# EM.net
KiCad netlist of a schematic drawn in Altium Designer
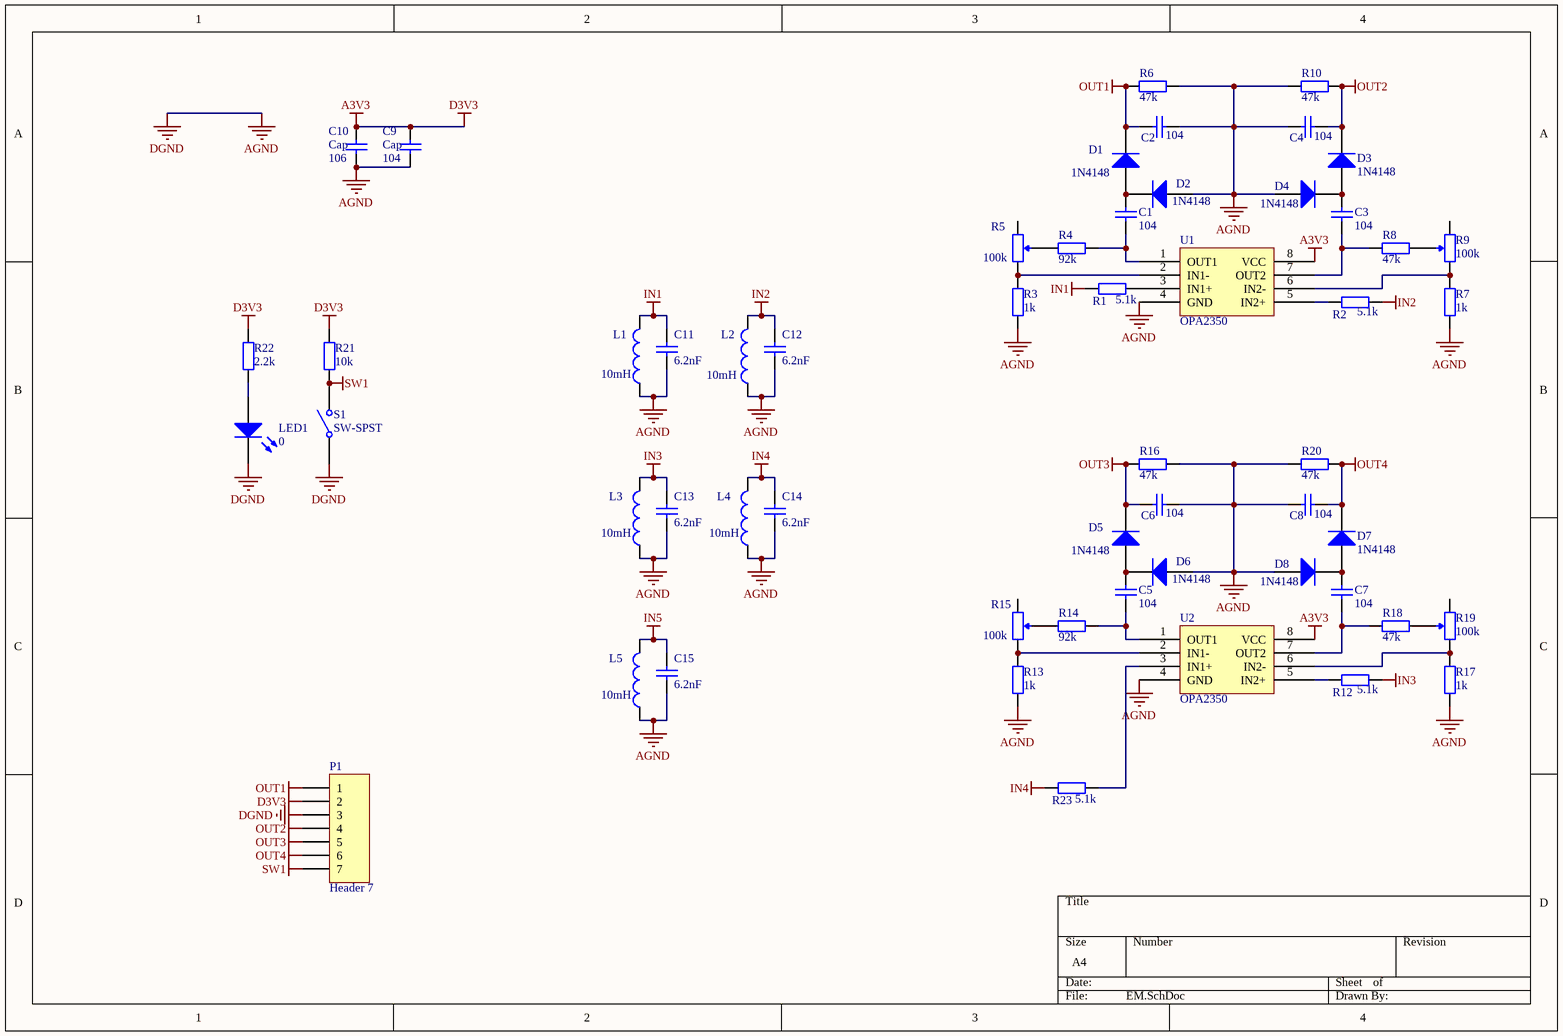
[diagram p0: EM.SchDoc]

(export (version "E")
  (design (tool "Eeschema 10.0.6"))
  (components
    (comp (ref "C1")
      (value "104")
      (footprint "0603C")
      (description "Capacitor")
      (fields (field (name "Comment") "Cap") (field (name "PUBLISHER") "Altium Limited"))
      (libsource (lib "Schlib1") (part "Cap"))
    )
    (comp (ref "C2")
      (value "104")
      (footprint "0603C")
      (description "Capacitor")
      (fields (field (name "Comment") "Cap") (field (name "PUBLISHER") "Altium Limited"))
      (libsource (lib "Schlib1") (part "Cap"))
    )
    (comp (ref "C3")
      (value "104")
      (footprint "0603C")
      (description "Capacitor")
      (fields (field (name "Comment") "Cap") (field (name "PUBLISHER") "Altium Limited"))
      (libsource (lib "Schlib1") (part "Cap"))
    )
    (comp (ref "C4")
      (value "104")
      (footprint "0603C")
      (description "Capacitor")
      (fields (field (name "Comment") "Cap") (field (name "PUBLISHER") "Altium Limited"))
      (libsource (lib "Schlib1") (part "Cap"))
    )
    (comp (ref "C5")
      (value "104")
      (footprint "0603C")
      (description "Capacitor")
      (fields (field (name "Comment") "Cap") (field (name "PUBLISHER") "Altium Limited"))
      (libsource (lib "Schlib1") (part "Cap"))
    )
    (comp (ref "C6")
      (value "104")
      (footprint "0603C")
      (description "Capacitor")
      (fields (field (name "Comment") "Cap") (field (name "PUBLISHER") "Altium Limited"))
      (libsource (lib "Schlib1") (part "Cap"))
    )
    (comp (ref "C7")
      (value "104")
      (footprint "0603C")
      (description "Capacitor")
      (fields (field (name "Comment") "Cap") (field (name "PUBLISHER") "Altium Limited"))
      (libsource (lib "Schlib1") (part "Cap"))
    )
    (comp (ref "C8")
      (value "104")
      (footprint "0603C")
      (description "Capacitor")
      (fields (field (name "Comment") "Cap") (field (name "PUBLISHER") "Altium Limited"))
      (libsource (lib "Schlib1") (part "Cap"))
    )
    (comp (ref "C9")
      (value "Cap")
      (footprint "0603C")
      (description "Capacitor")
      (fields (field (name "ALTIUM_VALUE") "104") (field (name "PUBLISHER") "Altium Limited"))
      (libsource (lib "Schlib1") (part "Cap"))
    )
    (comp (ref "C10")
      (value "Cap")
      (footprint "0805")
      (description "Capacitor")
      (fields (field (name "ALTIUM_VALUE") "106") (field (name "PUBLISHER") "Altium Limited"))
      (libsource (lib "Schlib1") (part "Cap"))
    )
    (comp (ref "C11")
      (value "6.2nF")
      (footprint "Cap2")
      (description "Capacitor")
      (fields (field (name "Comment") "Cap") (field (name "PUBLISHER") "Altium Limited"))
      (libsource (lib "Schlib1") (part "Cap"))
    )
    (comp (ref "C12")
      (value "6.2nF")
      (footprint "Cap2")
      (description "Capacitor")
      (fields (field (name "Comment") "Cap") (field (name "PUBLISHER") "Altium Limited"))
      (libsource (lib "Schlib1") (part "Cap"))
    )
    (comp (ref "C13")
      (value "6.2nF")
      (footprint "Cap2")
      (description "Capacitor")
      (fields (field (name "Comment") "Cap") (field (name "PUBLISHER") "Altium Limited"))
      (libsource (lib "Schlib1") (part "Cap"))
    )
    (comp (ref "C14")
      (value "6.2nF")
      (footprint "Cap2")
      (description "Capacitor")
      (fields (field (name "Comment") "Cap") (field (name "PUBLISHER") "Altium Limited"))
      (libsource (lib "Schlib1") (part "Cap"))
    )
    (comp (ref "C15")
      (value "6.2nF")
      (footprint "Cap2")
      (description "Capacitor")
      (fields (field (name "Comment") "Cap") (field (name "PUBLISHER") "Altium Limited"))
      (libsource (lib "Schlib1") (part "Cap"))
    )
    (comp (ref "D1")
      (value "1N4148")
      (footprint "SOD123")
      (description "Default Diode")
      (fields (field (name "PUBLISHER") "Altium Limited"))
      (libsource (lib "Schlib1") (part "Diode_2"))
    )
    (comp (ref "D2")
      (value "1N4148")
      (footprint "SOD123")
      (description "Default Diode")
      (fields (field (name "PUBLISHER") "Altium Limited"))
      (libsource (lib "Schlib1") (part "Diode_2"))
    )
    (comp (ref "D3")
      (value "1N4148")
      (footprint "SOD123")
      (description "Default Diode")
      (fields (field (name "PUBLISHER") "Altium Limited"))
      (libsource (lib "Schlib1") (part "Diode_2"))
    )
    (comp (ref "D4")
      (value "1N4148")
      (footprint "SOD123")
      (description "Default Diode")
      (fields (field (name "PUBLISHER") "Altium Limited"))
      (libsource (lib "Schlib1") (part "Diode_2"))
    )
    (comp (ref "D5")
      (value "1N4148")
      (footprint "SOD123")
      (description "Default Diode")
      (fields (field (name "PUBLISHER") "Altium Limited"))
      (libsource (lib "Schlib1") (part "Diode_2"))
    )
    (comp (ref "D6")
      (value "1N4148")
      (footprint "SOD123")
      (description "Default Diode")
      (fields (field (name "PUBLISHER") "Altium Limited"))
      (libsource (lib "Schlib1") (part "Diode_2"))
    )
    (comp (ref "D7")
      (value "1N4148")
      (footprint "SOD123")
      (description "Default Diode")
      (fields (field (name "PUBLISHER") "Altium Limited"))
      (libsource (lib "Schlib1") (part "Diode_2"))
    )
    (comp (ref "D8")
      (value "1N4148")
      (footprint "SOD123")
      (description "Default Diode")
      (fields (field (name "PUBLISHER") "Altium Limited"))
      (libsource (lib "Schlib1") (part "Diode_2"))
    )
    (comp (ref "L1")
      (value "10mH")
      (footprint "L2")
      (description "Inductor")
      (fields (field (name "PUBLISHER") "Altium Limited"))
      (libsource (lib "") (part "Inductor_2_1"))
    )
    (comp (ref "L2")
      (value "10mH")
      (footprint "L2")
      (description "Inductor")
      (fields (field (name "PUBLISHER") "Altium Limited"))
      (libsource (lib "") (part "Inductor_2_1"))
    )
    (comp (ref "L3")
      (value "10mH")
      (footprint "L2")
      (description "Inductor")
      (fields (field (name "PUBLISHER") "Altium Limited"))
      (libsource (lib "Schlib1") (part "Inductor_2"))
    )
    (comp (ref "L4")
      (value "10mH")
      (footprint "L2")
      (description "Inductor")
      (fields (field (name "PUBLISHER") "Altium Limited"))
      (libsource (lib "Schlib1") (part "Inductor_2"))
    )
    (comp (ref "L5")
      (value "10mH")
      (footprint "L2")
      (description "Inductor")
      (fields (field (name "PUBLISHER") "Altium Limited"))
      (libsource (lib "Schlib1") (part "Inductor_2"))
    )
    (comp (ref "LED1")
      (value "0")
      (footprint "0603C")
      (description "Typical RED, GREEN, YELLOW, AMBER GaAs LED")
      (fields (field (name "PUBLISHER") "Altium Limited"))
      (libsource (lib "Schlib1") (part "LED2"))
    )
    (comp (ref "P1")
      (value "Header 7")
      (footprint "HDR1X7")
      (description "Header, 7-Pin")
      (fields (field (name "PUBLISHER") "Altium Limited"))
      (libsource (lib "Miscellaneous Connectors") (part "Header 7"))
    )
    (comp (ref "R1")
      (value "5.1k")
      (footprint "0603C")
      (description "Resistor")
      (fields (field (name "Comment") "Res2") (field (name "PUBLISHER") "Altium Limited"))
      (libsource (lib "") (part "Res2_1"))
    )
    (comp (ref "R2")
      (value "5.1k")
      (footprint "0603C")
      (description "Resistor")
      (fields (field (name "Comment") "Res2") (field (name "PUBLISHER") "Altium Limited"))
      (libsource (lib "") (part "Res2_2"))
    )
    (comp (ref "R3")
      (value "1k")
      (footprint "0603C")
      (description "Resistor")
      (fields (field (name "Comment") "Res2") (field (name "PUBLISHER") "Altium Limited"))
      (libsource (lib "Schlib1") (part "Res2"))
    )
    (comp (ref "R4")
      (value "92k")
      (footprint "0603C")
      (description "Resistor")
      (fields (field (name "Comment") "Res2") (field (name "PUBLISHER") "Altium Limited"))
      (libsource (lib "") (part "Res2_1"))
    )
    (comp (ref "R5")
      (value "100k")
      (footprint "W102/3296w")
      (description "Resistor")
      (fields (field (name "Comment") "Res2") (field (name "PUBLISHER") "Altium Limited"))
      (libsource (lib "") (part "RP_1"))
    )
    (comp (ref "R6")
      (value "47k")
      (footprint "0603C")
      (description "Resistor")
      (fields (field (name "Comment") "Res2") (field (name "PUBLISHER") "Altium Limited"))
      (libsource (lib "") (part "Res2_1"))
    )
    (comp (ref "R7")
      (value "1k")
      (footprint "0603C")
      (description "Resistor")
      (fields (field (name "Comment") "Res2") (field (name "PUBLISHER") "Altium Limited"))
      (libsource (lib "") (part "Res2_1"))
    )
    (comp (ref "R8")
      (value "47k")
      (footprint "0603C")
      (description "Resistor")
      (fields (field (name "Comment") "Res2") (field (name "PUBLISHER") "Altium Limited"))
      (libsource (lib "") (part "Res2_2"))
    )
    (comp (ref "R9")
      (value "100k")
      (footprint "W102/3296w")
      (description "Resistor")
      (fields (field (name "Comment") "Res2") (field (name "PUBLISHER") "Altium Limited"))
      (libsource (lib "Schlib1") (part "RP"))
    )
    (comp (ref "R10")
      (value "47k")
      (footprint "0603C")
      (description "Resistor")
      (fields (field (name "Comment") "Res2") (field (name "PUBLISHER") "Altium Limited"))
      (libsource (lib "") (part "Res2_2"))
    )
    (comp (ref "R12")
      (value "5.1k")
      (footprint "0603C")
      (description "Resistor")
      (fields (field (name "Comment") "Res2") (field (name "PUBLISHER") "Altium Limited"))
      (libsource (lib "") (part "Res2_2"))
    )
    (comp (ref "R13")
      (value "1k")
      (footprint "0603C")
      (description "Resistor")
      (fields (field (name "Comment") "Res2") (field (name "PUBLISHER") "Altium Limited"))
      (libsource (lib "Schlib1") (part "Res2"))
    )
    (comp (ref "R14")
      (value "92k")
      (footprint "0603C")
      (description "Resistor")
      (fields (field (name "Comment") "Res2") (field (name "PUBLISHER") "Altium Limited"))
      (libsource (lib "") (part "Res2_1"))
    )
    (comp (ref "R15")
      (value "100k")
      (footprint "W102/3296w")
      (description "Resistor")
      (fields (field (name "Comment") "Res2") (field (name "PUBLISHER") "Altium Limited"))
      (libsource (lib "") (part "RP_1"))
    )
    (comp (ref "R16")
      (value "47k")
      (footprint "0603C")
      (description "Resistor")
      (fields (field (name "Comment") "Res2") (field (name "PUBLISHER") "Altium Limited"))
      (libsource (lib "") (part "Res2_1"))
    )
    (comp (ref "R17")
      (value "1k")
      (footprint "0603C")
      (description "Resistor")
      (fields (field (name "Comment") "Res2") (field (name "PUBLISHER") "Altium Limited"))
      (libsource (lib "") (part "Res2_1"))
    )
    (comp (ref "R18")
      (value "47k")
      (footprint "0603C")
      (description "Resistor")
      (fields (field (name "Comment") "Res2") (field (name "PUBLISHER") "Altium Limited"))
      (libsource (lib "") (part "Res2_2"))
    )
    (comp (ref "R19")
      (value "100k")
      (footprint "W102/3296w")
      (description "Resistor")
      (fields (field (name "Comment") "Res2") (field (name "PUBLISHER") "Altium Limited"))
      (libsource (lib "Schlib1") (part "RP"))
    )
    (comp (ref "R20")
      (value "47k")
      (footprint "0603C")
      (description "Resistor")
      (fields (field (name "Comment") "Res2") (field (name "PUBLISHER") "Altium Limited"))
      (libsource (lib "") (part "Res2_2"))
    )
    (comp (ref "R21")
      (value "10k")
      (footprint "0603C")
      (description "Resistor")
      (fields (field (name "Comment") "Res2") (field (name "PUBLISHER") "Altium Limited"))
      (libsource (lib "Schlib1") (part "Res2"))
    )
    (comp (ref "R22")
      (value "2.2k")
      (footprint "0603R")
      (description "Resistor")
      (fields (field (name "Comment") "Res2") (field (name "PUBLISHER") "Altium Limited"))
      (libsource (lib "Schlib1") (part "Res2"))
    )
    (comp (ref "R23")
      (value "5.1k")
      (footprint "0603C")
      (description "Resistor")
      (fields (field (name "Comment") "Res2") (field (name "PUBLISHER") "Altium Limited"))
      (libsource (lib "") (part "Res2_1"))
    )
    (comp (ref "S1")
      (value "SW-SPST")
      (footprint "SW_REED")
      (description "Single-Pole, Single-Throw Switch")
      (fields (field (name "PUBLISHER") "Altium Limited"))
      (libsource (lib "Miscellaneous Devices") (part "SW-SPST"))
    )
    (comp (ref "U1") (value "OPA2350") (footprint "SOIC-8") (libsource (lib "Schlib1") (part "OPA2350")))
    (comp (ref "U2") (value "OPA2350") (footprint "SOIC-8") (libsource (lib "Schlib1") (part "OPA2350")))
  )
  (nets
    (net (code "1") (name "A3V3") (class "Default")
      (node (ref "C10") (pin "2") (pinfunction "2_2") (pintype "passive"))
      (node (ref "C9") (pin "2") (pinfunction "2_2") (pintype "passive"))
      (node (ref "P1") (pin "2") (pinfunction "2_2") (pintype "passive"))
      (node (ref "R21") (pin "2") (pinfunction "2_2") (pintype "passive"))
      (node (ref "R22") (pin "2") (pinfunction "2_2") (pintype "passive"))
      (node (ref "U1") (pin "8") (pinfunction "VCC_8") (pintype "passive"))
      (node (ref "U2") (pin "8") (pinfunction "VCC_8") (pintype "passive"))
    )
    (net (code "2") (name "AGND") (class "Default")
      (node (ref "C10") (pin "1") (pinfunction "1_1") (pintype "passive"))
      (node (ref "C11") (pin "1") (pinfunction "1_1") (pintype "passive"))
      (node (ref "C12") (pin "1") (pinfunction "1_1") (pintype "passive"))
      (node (ref "C13") (pin "1") (pinfunction "1_1") (pintype "passive"))
      (node (ref "C14") (pin "1") (pinfunction "1_1") (pintype "passive"))
      (node (ref "C15") (pin "1") (pinfunction "1_1") (pintype "passive"))
      (node (ref "C2") (pin "2") (pinfunction "2_2") (pintype "passive"))
      (node (ref "C4") (pin "2") (pinfunction "2_2") (pintype "passive"))
      (node (ref "C6") (pin "2") (pinfunction "2_2") (pintype "passive"))
      (node (ref "C8") (pin "2") (pinfunction "2_2") (pintype "passive"))
      (node (ref "C9") (pin "1") (pinfunction "1_1") (pintype "passive"))
      (node (ref "D2") (pin "1") (pinfunction "A_1") (pintype "passive"))
      (node (ref "D4") (pin "1") (pinfunction "A_1") (pintype "passive"))
      (node (ref "D6") (pin "1") (pinfunction "A_1") (pintype "passive"))
      (node (ref "D8") (pin "1") (pinfunction "A_1") (pintype "passive"))
      (node (ref "L1") (pin "1") (pinfunction "1_1") (pintype "passive"))
      (node (ref "L2") (pin "1") (pinfunction "1_1") (pintype "passive"))
      (node (ref "L3") (pin "2") (pinfunction "2_2") (pintype "passive"))
      (node (ref "L4") (pin "2") (pinfunction "2_2") (pintype "passive"))
      (node (ref "L5") (pin "2") (pinfunction "2_2") (pintype "passive"))
      (node (ref "LED1") (pin "2") (pinfunction "K_2") (pintype "passive"))
      (node (ref "P1") (pin "3") (pinfunction "3_3") (pintype "passive"))
      (node (ref "R10") (pin "2") (pinfunction "2_2") (pintype "passive"))
      (node (ref "R13") (pin "1") (pinfunction "1_1") (pintype "passive"))
      (node (ref "R16") (pin "2") (pinfunction "2_2") (pintype "passive"))
      (node (ref "R17") (pin "1") (pinfunction "1_1") (pintype "passive"))
      (node (ref "R20") (pin "2") (pinfunction "2_2") (pintype "passive"))
      (node (ref "R3") (pin "1") (pinfunction "1_1") (pintype "passive"))
      (node (ref "R6") (pin "2") (pinfunction "2_2") (pintype "passive"))
      (node (ref "R7") (pin "1") (pinfunction "1_1") (pintype "passive"))
      (node (ref "S1") (pin "1") (pinfunction "COMMON_1") (pintype "passive"))
      (node (ref "U1") (pin "4") (pinfunction "GND_4") (pintype "passive"))
      (node (ref "U2") (pin "4") (pinfunction "GND_4") (pintype "passive"))
    )
    (net (code "3") (name "IN1") (class "Default")
      (node (ref "C11") (pin "2") (pinfunction "2_2") (pintype "passive"))
      (node (ref "L1") (pin "2") (pinfunction "2_2") (pintype "passive"))
      (node (ref "R1") (pin "1") (pinfunction "1_1") (pintype "passive"))
    )
    (net (code "4") (name "IN2") (class "Default")
      (node (ref "C12") (pin "2") (pinfunction "2_2") (pintype "passive"))
      (node (ref "L2") (pin "2") (pinfunction "2_2") (pintype "passive"))
      (node (ref "R2") (pin "1") (pinfunction "1_1") (pintype "passive"))
    )
    (net (code "5") (name "IN3") (class "Default")
      (node (ref "C13") (pin "2") (pinfunction "2_2") (pintype "passive"))
      (node (ref "L3") (pin "1") (pinfunction "1_1") (pintype "passive"))
      (node (ref "R12") (pin "1") (pinfunction "1_1") (pintype "passive"))
    )
    (net (code "6") (name "IN4") (class "Default")
      (node (ref "C14") (pin "2") (pinfunction "2_2") (pintype "passive"))
      (node (ref "L4") (pin "1") (pinfunction "1_1") (pintype "passive"))
      (node (ref "R23") (pin "1") (pinfunction "1_1") (pintype "passive"))
    )
    (net (code "7") (name "IN5") (class "Default")
      (node (ref "C15") (pin "2") (pinfunction "2_2") (pintype "passive"))
      (node (ref "L5") (pin "1") (pinfunction "1_1") (pintype "passive"))
    )
    (net (code "8") (name "Net-(D1-A)") (class "Default")
      (node (ref "C1") (pin "2") (pinfunction "2_2") (pintype "passive"))
      (node (ref "D1") (pin "1") (pinfunction "A_1") (pintype "passive"))
      (node (ref "D2") (pin "2") (pinfunction "K_2") (pintype "passive"))
    )
    (net (code "9") (name "Net-(D3-A)") (class "Default")
      (node (ref "C3") (pin "2") (pinfunction "2_2") (pintype "passive"))
      (node (ref "D3") (pin "1") (pinfunction "A_1") (pintype "passive"))
      (node (ref "D4") (pin "2") (pinfunction "K_2") (pintype "passive"))
    )
    (net (code "10") (name "Net-(D5-A)") (class "Default")
      (node (ref "C5") (pin "2") (pinfunction "2_2") (pintype "passive"))
      (node (ref "D5") (pin "1") (pinfunction "A_1") (pintype "passive"))
      (node (ref "D6") (pin "2") (pinfunction "K_2") (pintype "passive"))
    )
    (net (code "11") (name "Net-(D7-A)") (class "Default")
      (node (ref "C7") (pin "2") (pinfunction "2_2") (pintype "passive"))
      (node (ref "D7") (pin "1") (pinfunction "A_1") (pintype "passive"))
      (node (ref "D8") (pin "2") (pinfunction "K_2") (pintype "passive"))
    )
    (net (code "12") (name "Net-(LED1-A)") (class "Default")
      (node (ref "LED1") (pin "1") (pinfunction "A_1") (pintype "passive"))
      (node (ref "R22") (pin "1") (pinfunction "1_1") (pintype "passive"))
    )
    (net (code "13") (name "Net-(R5-TAP)") (class "Default")
      (node (ref "R4") (pin "1") (pinfunction "1_1") (pintype "passive"))
      (node (ref "R5") (pin "3") (pinfunction "TAP_3") (pintype "passive"))
    )
    (net (code "14") (name "Net-(R9-TAP)") (class "Default")
      (node (ref "R8") (pin "1") (pinfunction "1_1") (pintype "passive"))
      (node (ref "R9") (pin "3") (pinfunction "TAP_3") (pintype "passive"))
    )
    (net (code "15") (name "Net-(R15-TAP)") (class "Default")
      (node (ref "R14") (pin "1") (pinfunction "1_1") (pintype "passive"))
      (node (ref "R15") (pin "3") (pinfunction "TAP_3") (pintype "passive"))
    )
    (net (code "16") (name "Net-(R19-TAP)") (class "Default")
      (node (ref "R18") (pin "1") (pinfunction "1_1") (pintype "passive"))
      (node (ref "R19") (pin "3") (pinfunction "TAP_3") (pintype "passive"))
    )
    (net (code "17") (name "Net-(U1-IN1+)") (class "Default")
      (node (ref "R1") (pin "2") (pinfunction "2_2") (pintype "passive"))
      (node (ref "U1") (pin "3") (pinfunction "IN1+_3") (pintype "passive"))
    )
    (net (code "18") (name "Net-(U1-IN1-)") (class "Default")
      (node (ref "R3") (pin "2") (pinfunction "2_2") (pintype "passive"))
      (node (ref "R5") (pin "1") (pinfunction "1_1") (pintype "passive"))
      (node (ref "U1") (pin "2") (pinfunction "IN1-_2") (pintype "passive"))
    )
    (net (code "19") (name "Net-(U1-IN2+)") (class "Default")
      (node (ref "R2") (pin "2") (pinfunction "2_2") (pintype "passive"))
      (node (ref "U1") (pin "5") (pinfunction "IN2+_5") (pintype "passive"))
    )
    (net (code "20") (name "Net-(U1-IN2-)") (class "Default")
      (node (ref "R7") (pin "2") (pinfunction "2_2") (pintype "passive"))
      (node (ref "R9") (pin "1") (pinfunction "1_1") (pintype "passive"))
      (node (ref "U1") (pin "6") (pinfunction "IN2-_6") (pintype "passive"))
    )
    (net (code "21") (name "Net-(U1-OUT1)") (class "Default")
      (node (ref "C1") (pin "1") (pinfunction "1_1") (pintype "passive"))
      (node (ref "R4") (pin "2") (pinfunction "2_2") (pintype "passive"))
      (node (ref "U1") (pin "1") (pinfunction "OUT1_1") (pintype "passive"))
    )
    (net (code "22") (name "Net-(U1-OUT2)") (class "Default")
      (node (ref "C3") (pin "1") (pinfunction "1_1") (pintype "passive"))
      (node (ref "R8") (pin "2") (pinfunction "2_2") (pintype "passive"))
      (node (ref "U1") (pin "7") (pinfunction "OUT2_7") (pintype "passive"))
    )
    (net (code "23") (name "Net-(U2-IN1+)") (class "Default")
      (node (ref "R23") (pin "2") (pinfunction "2_2") (pintype "passive"))
      (node (ref "U2") (pin "3") (pinfunction "IN1+_3") (pintype "passive"))
    )
    (net (code "24") (name "Net-(U2-IN1-)") (class "Default")
      (node (ref "R13") (pin "2") (pinfunction "2_2") (pintype "passive"))
      (node (ref "R15") (pin "1") (pinfunction "1_1") (pintype "passive"))
      (node (ref "U2") (pin "2") (pinfunction "IN1-_2") (pintype "passive"))
    )
    (net (code "25") (name "Net-(U2-IN2+)") (class "Default")
      (node (ref "R12") (pin "2") (pinfunction "2_2") (pintype "passive"))
      (node (ref "U2") (pin "5") (pinfunction "IN2+_5") (pintype "passive"))
    )
    (net (code "26") (name "Net-(U2-IN2-)") (class "Default")
      (node (ref "R17") (pin "2") (pinfunction "2_2") (pintype "passive"))
      (node (ref "R19") (pin "1") (pinfunction "1_1") (pintype "passive"))
      (node (ref "U2") (pin "6") (pinfunction "IN2-_6") (pintype "passive"))
    )
    (net (code "27") (name "Net-(U2-OUT1)") (class "Default")
      (node (ref "C5") (pin "1") (pinfunction "1_1") (pintype "passive"))
      (node (ref "R14") (pin "2") (pinfunction "2_2") (pintype "passive"))
      (node (ref "U2") (pin "1") (pinfunction "OUT1_1") (pintype "passive"))
    )
    (net (code "28") (name "Net-(U2-OUT2)") (class "Default")
      (node (ref "C7") (pin "1") (pinfunction "1_1") (pintype "passive"))
      (node (ref "R18") (pin "2") (pinfunction "2_2") (pintype "passive"))
      (node (ref "U2") (pin "7") (pinfunction "OUT2_7") (pintype "passive"))
    )
    (net (code "29") (name "OUT1") (class "Default")
      (node (ref "C2") (pin "1") (pinfunction "1_1") (pintype "passive"))
      (node (ref "D1") (pin "2") (pinfunction "K_2") (pintype "passive"))
      (node (ref "P1") (pin "1") (pinfunction "1_1") (pintype "passive"))
      (node (ref "R6") (pin "1") (pinfunction "1_1") (pintype "passive"))
    )
    (net (code "30") (name "OUT2") (class "Default")
      (node (ref "C4") (pin "1") (pinfunction "1_1") (pintype "passive"))
      (node (ref "D3") (pin "2") (pinfunction "K_2") (pintype "passive"))
      (node (ref "P1") (pin "4") (pinfunction "4_4") (pintype "passive"))
      (node (ref "R10") (pin "1") (pinfunction "1_1") (pintype "passive"))
    )
    (net (code "31") (name "OUT3") (class "Default")
      (node (ref "C6") (pin "1") (pinfunction "1_1") (pintype "passive"))
      (node (ref "D5") (pin "2") (pinfunction "K_2") (pintype "passive"))
      (node (ref "P1") (pin "5") (pinfunction "5_5") (pintype "passive"))
      (node (ref "R16") (pin "1") (pinfunction "1_1") (pintype "passive"))
    )
    (net (code "32") (name "OUT4") (class "Default")
      (node (ref "C8") (pin "1") (pinfunction "1_1") (pintype "passive"))
      (node (ref "D7") (pin "2") (pinfunction "K_2") (pintype "passive"))
      (node (ref "P1") (pin "6") (pinfunction "6_6") (pintype "passive"))
      (node (ref "R20") (pin "1") (pinfunction "1_1") (pintype "passive"))
    )
    (net (code "33") (name "SW1") (class "Default")
      (node (ref "P1") (pin "7") (pinfunction "7_7") (pintype "passive"))
      (node (ref "R21") (pin "1") (pinfunction "1_1") (pintype "passive"))
      (node (ref "S1") (pin "2") (pinfunction "NO_2") (pintype "passive"))
    )
    (net (code "34") (name "unconnected-(R5-Pad3)") (class "Default")
      (node (ref "R5") (pin "3") (pinfunction "3_3") (pintype "passive"))
    )
    (net (code "35") (name "unconnected-(R9-Pad3)") (class "Default")
      (node (ref "R9") (pin "3") (pinfunction "3_3") (pintype "passive"))
    )
    (net (code "36") (name "unconnected-(R15-Pad3)") (class "Default")
      (node (ref "R15") (pin "3") (pinfunction "3_3") (pintype "passive"))
    )
    (net (code "37") (name "unconnected-(R19-Pad3)") (class "Default")
      (node (ref "R19") (pin "3") (pinfunction "3_3") (pintype "passive"))
    )
  )
)
